# INA219Input.net
KiCad netlist of a schematic drawn in Altium Designer
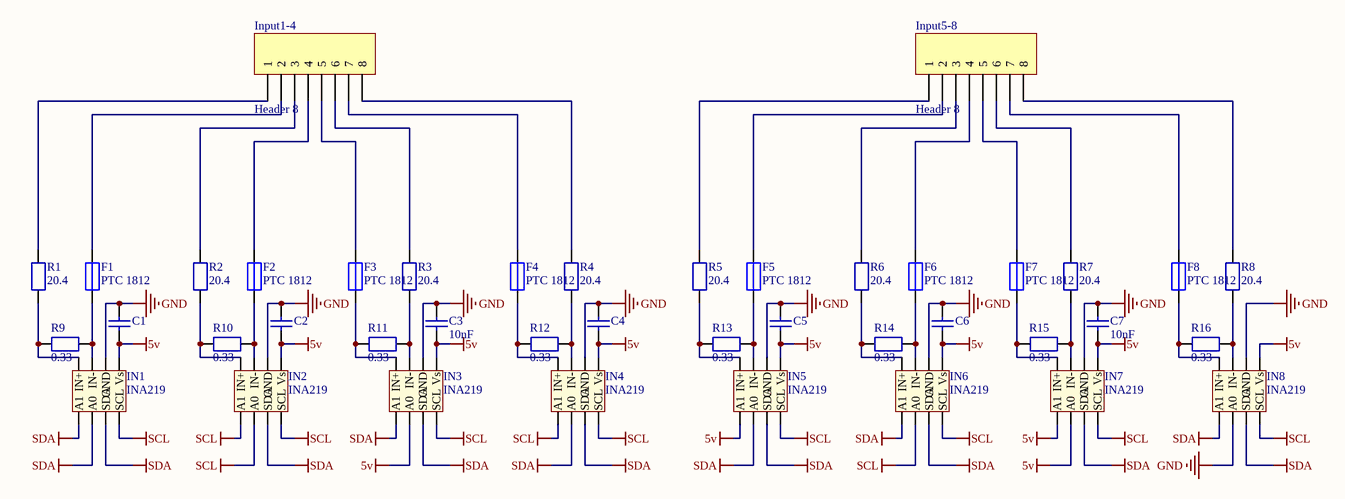
[diagram p0: INA219Input.SchDoc]

(export (version "E")
  (design (tool "Eeschema 10.0.6"))
  (components
    (comp (ref "C1")
      (value "~")
      (footprint "1\" ceramic Radial Cap")
      (description "1\" ceramic Radial Cap")
      (libsource (lib "Capacitors") (part "1{dblquote} ceramic Radial Cap"))
    )
    (comp (ref "C2")
      (value "~")
      (footprint "1\" ceramic Radial Cap")
      (description "1\" ceramic Radial Cap")
      (libsource (lib "Capacitors") (part "1{dblquote} ceramic Radial Cap"))
    )
    (comp (ref "C3")
      (value "10nF")
      (footprint "1\" ceramic Radial Cap")
      (description "1\" ceramic Radial Cap")
      (libsource (lib "Capacitors") (part "1{dblquote} ceramic Radial Cap"))
    )
    (comp (ref "C4")
      (value "~")
      (footprint "1\" ceramic Radial Cap")
      (description "1\" ceramic Radial Cap")
      (libsource (lib "Capacitors") (part "1{dblquote} ceramic Radial Cap"))
    )
    (comp (ref "C5")
      (value "~")
      (footprint "1\" ceramic Radial Cap")
      (description "1\" ceramic Radial Cap")
      (libsource (lib "Capacitors") (part "1{dblquote} ceramic Radial Cap"))
    )
    (comp (ref "C6")
      (value "~")
      (footprint "1\" ceramic Radial Cap")
      (description "1\" ceramic Radial Cap")
      (libsource (lib "Capacitors") (part "1{dblquote} ceramic Radial Cap"))
    )
    (comp (ref "C7")
      (value "10nF")
      (footprint "1\" ceramic Radial Cap")
      (description "1\" ceramic Radial Cap")
      (libsource (lib "Capacitors") (part "1{dblquote} ceramic Radial Cap"))
    )
    (comp (ref "F1")
      (value "PTC 1812")
      (footprint "0ZCG PTC 1812")
      (libsource (lib "Fuses") (part "PTC 1812 Bel Fuse"))
    )
    (comp (ref "F2")
      (value "PTC 1812")
      (footprint "0ZCG PTC 1812")
      (libsource (lib "Fuses") (part "PTC 1812 Bel Fuse"))
    )
    (comp (ref "F3")
      (value "PTC 1812")
      (footprint "0ZCG PTC 1812")
      (libsource (lib "Fuses") (part "PTC 1812 Bel Fuse"))
    )
    (comp (ref "F4")
      (value "PTC 1812")
      (footprint "0ZCG PTC 1812")
      (libsource (lib "Fuses") (part "PTC 1812 Bel Fuse"))
    )
    (comp (ref "F5")
      (value "PTC 1812")
      (footprint "0ZCG PTC 1812")
      (libsource (lib "Fuses") (part "PTC 1812 Bel Fuse"))
    )
    (comp (ref "F6")
      (value "PTC 1812")
      (footprint "0ZCG PTC 1812")
      (libsource (lib "Fuses") (part "PTC 1812 Bel Fuse"))
    )
    (comp (ref "F7")
      (value "PTC 1812")
      (footprint "0ZCG PTC 1812")
      (libsource (lib "Fuses") (part "PTC 1812 Bel Fuse"))
    )
    (comp (ref "F8")
      (value "PTC 1812")
      (footprint "0ZCG PTC 1812")
      (libsource (lib "Fuses") (part "PTC 1812 Bel Fuse"))
    )
    (comp (ref "IN1")
      (value "INA219")
      (footprint "INA219-D-SOIC")
      (libsource (lib "Miscellaneous IC's") (part "INA219-D-SOIC"))
    )
    (comp (ref "IN2")
      (value "INA219")
      (footprint "INA219-D-SOIC")
      (libsource (lib "Miscellaneous IC's") (part "INA219-D-SOIC"))
    )
    (comp (ref "IN3")
      (value "INA219")
      (footprint "INA219-D-SOIC")
      (libsource (lib "Miscellaneous IC's") (part "INA219-D-SOIC"))
    )
    (comp (ref "IN4")
      (value "INA219")
      (footprint "INA219-D-SOIC")
      (libsource (lib "Miscellaneous IC's") (part "INA219-D-SOIC"))
    )
    (comp (ref "IN5")
      (value "INA219")
      (footprint "INA219-D-SOIC")
      (libsource (lib "Miscellaneous IC's") (part "INA219-D-SOIC"))
    )
    (comp (ref "IN6")
      (value "INA219")
      (footprint "INA219-D-SOIC")
      (libsource (lib "Miscellaneous IC's") (part "INA219-D-SOIC"))
    )
    (comp (ref "IN7")
      (value "INA219")
      (footprint "INA219-D-SOIC")
      (libsource (lib "Miscellaneous IC's") (part "INA219-D-SOIC"))
    )
    (comp (ref "IN8")
      (value "INA219")
      (footprint "INA219-D-SOIC")
      (libsource (lib "Miscellaneous IC's") (part "INA219-D-SOIC"))
    )
    (comp (ref "Input1-4")
      (value "Header 8")
      (footprint "HDR1X8")
      (description "Header, 8-Pin")
      (fields (field (name "PUBLISHER") "Altium Limited"))
      (libsource (lib "Miscellaneous Connectors") (part "Header 8"))
    )
    (comp (ref "Input5-8")
      (value "Header 8")
      (footprint "HDR1X8")
      (description "Header, 8-Pin")
      (fields (field (name "PUBLISHER") "Altium Limited"))
      (libsource (lib "Miscellaneous Connectors") (part "Header 8"))
    )
    (comp (ref "R1")
      (value "20.4")
      (footprint "Axial 0.85 5W")
      (libsource (lib "Resistors") (part "Axial 0.85{dblquote} 5W"))
    )
    (comp (ref "R2")
      (value "20.4")
      (footprint "Axial 0.85 5W")
      (libsource (lib "Resistors") (part "Axial 0.85{dblquote} 5W"))
    )
    (comp (ref "R3")
      (value "20.4")
      (footprint "Axial 0.85 5W")
      (libsource (lib "Resistors") (part "Axial 0.85{dblquote} 5W"))
    )
    (comp (ref "R4")
      (value "20.4")
      (footprint "Axial 0.85 5W")
      (libsource (lib "Resistors") (part "Axial 0.85{dblquote} 5W"))
    )
    (comp (ref "R5")
      (value "20.4")
      (footprint "Axial 0.85 5W")
      (libsource (lib "Resistors") (part "Axial 0.85{dblquote} 5W"))
    )
    (comp (ref "R6")
      (value "20.4")
      (footprint "Axial 0.85 5W")
      (libsource (lib "Resistors") (part "Axial 0.85{dblquote} 5W"))
    )
    (comp (ref "R7")
      (value "20.4")
      (footprint "Axial 0.85 5W")
      (libsource (lib "Resistors") (part "Axial 0.85{dblquote} 5W"))
    )
    (comp (ref "R8")
      (value "20.4")
      (footprint "Axial 0.85 5W")
      (libsource (lib "Resistors") (part "Axial 0.85{dblquote} 5W"))
    )
    (comp (ref "R9")
      (value "0.33")
      (footprint "1206 SMD 1/4W")
      (libsource (lib "Resistors") (part "1206 SMD 1/4W"))
    )
    (comp (ref "R10")
      (value "0.33")
      (footprint "1206 SMD 1/4W")
      (libsource (lib "Resistors") (part "1206 SMD 1/4W"))
    )
    (comp (ref "R11")
      (value "0.33")
      (footprint "1206 SMD 1/4W")
      (libsource (lib "Resistors") (part "1206 SMD 1/4W"))
    )
    (comp (ref "R12")
      (value "0.33")
      (footprint "1206 SMD 1/4W")
      (libsource (lib "Resistors") (part "1206 SMD 1/4W"))
    )
    (comp (ref "R13")
      (value "0.33")
      (footprint "1206 SMD 1/4W")
      (libsource (lib "Resistors") (part "1206 SMD 1/4W"))
    )
    (comp (ref "R14")
      (value "0.33")
      (footprint "1206 SMD 1/4W")
      (libsource (lib "Resistors") (part "1206 SMD 1/4W"))
    )
    (comp (ref "R15")
      (value "0.33")
      (footprint "1206 SMD 1/4W")
      (libsource (lib "Resistors") (part "1206 SMD 1/4W"))
    )
    (comp (ref "R16")
      (value "0.33")
      (footprint "1206 SMD 1/4W")
      (libsource (lib "Resistors") (part "1206 SMD 1/4W"))
    )
  )
  (nets
    (net (code "1") (name "5v") (class "Default")
      (node (ref "C1") (pin "1") (pinfunction "1_1") (pintype "passive"))
      (node (ref "C2") (pin "1") (pinfunction "1_1") (pintype "passive"))
      (node (ref "C3") (pin "1") (pinfunction "1_1") (pintype "passive"))
      (node (ref "C4") (pin "1") (pinfunction "1_1") (pintype "passive"))
      (node (ref "C5") (pin "1") (pinfunction "1_1") (pintype "passive"))
      (node (ref "C6") (pin "1") (pinfunction "1_1") (pintype "passive"))
      (node (ref "C7") (pin "1") (pinfunction "1_1") (pintype "passive"))
      (node (ref "IN1") (pin "Vs") (pinfunction "Vs_Vs") (pintype "passive"))
      (node (ref "IN2") (pin "Vs") (pinfunction "Vs_Vs") (pintype "passive"))
      (node (ref "IN3") (pin "A0") (pinfunction "A0_A0") (pintype "passive"))
      (node (ref "IN3") (pin "Vs") (pinfunction "Vs_Vs") (pintype "passive"))
      (node (ref "IN4") (pin "Vs") (pinfunction "Vs_Vs") (pintype "passive"))
      (node (ref "IN5") (pin "A1") (pinfunction "A1_A1") (pintype "passive"))
      (node (ref "IN5") (pin "Vs") (pinfunction "Vs_Vs") (pintype "passive"))
      (node (ref "IN6") (pin "Vs") (pinfunction "Vs_Vs") (pintype "passive"))
      (node (ref "IN7") (pin "A0") (pinfunction "A0_A0") (pintype "passive"))
      (node (ref "IN7") (pin "A1") (pinfunction "A1_A1") (pintype "passive"))
      (node (ref "IN7") (pin "Vs") (pinfunction "Vs_Vs") (pintype "passive"))
      (node (ref "IN8") (pin "Vs") (pinfunction "Vs_Vs") (pintype "passive"))
    )
    (net (code "2") (name "GND") (class "Default")
      (node (ref "C1") (pin "2") (pinfunction "2_2") (pintype "passive"))
      (node (ref "C2") (pin "2") (pinfunction "2_2") (pintype "passive"))
      (node (ref "C3") (pin "2") (pinfunction "2_2") (pintype "passive"))
      (node (ref "C4") (pin "2") (pinfunction "2_2") (pintype "passive"))
      (node (ref "C5") (pin "2") (pinfunction "2_2") (pintype "passive"))
      (node (ref "C6") (pin "2") (pinfunction "2_2") (pintype "passive"))
      (node (ref "C7") (pin "2") (pinfunction "2_2") (pintype "passive"))
      (node (ref "IN1") (pin "GND") (pinfunction "GND_GND") (pintype "passive"))
      (node (ref "IN2") (pin "GND") (pinfunction "GND_GND") (pintype "passive"))
      (node (ref "IN3") (pin "GND") (pinfunction "GND_GND") (pintype "passive"))
      (node (ref "IN4") (pin "GND") (pinfunction "GND_GND") (pintype "passive"))
      (node (ref "IN5") (pin "GND") (pinfunction "GND_GND") (pintype "passive"))
      (node (ref "IN6") (pin "GND") (pinfunction "GND_GND") (pintype "passive"))
      (node (ref "IN7") (pin "GND") (pinfunction "GND_GND") (pintype "passive"))
      (node (ref "IN8") (pin "A0") (pinfunction "A0_A0") (pintype "passive"))
      (node (ref "IN8") (pin "GND") (pinfunction "GND_GND") (pintype "passive"))
    )
    (net (code "3") (name "Net-(F1-Pad1)") (class "Default")
      (node (ref "F1") (pin "1") (pinfunction "1_1") (pintype "passive"))
      (node (ref "IN1") (pin "IN-") (pinfunction "IN-_IN-") (pintype "passive"))
      (node (ref "R9") (pin "1") (pinfunction "1_1") (pintype "passive"))
    )
    (net (code "4") (name "Net-(F1-Pad2)") (class "Default")
      (node (ref "F1") (pin "2") (pinfunction "2_2") (pintype "passive"))
      (node (ref "Input1-4") (pin "2") (pinfunction "2_2") (pintype "passive"))
    )
    (net (code "5") (name "Net-(F2-Pad1)") (class "Default")
      (node (ref "F2") (pin "1") (pinfunction "1_1") (pintype "passive"))
      (node (ref "IN2") (pin "IN-") (pinfunction "IN-_IN-") (pintype "passive"))
      (node (ref "R10") (pin "1") (pinfunction "1_1") (pintype "passive"))
    )
    (net (code "6") (name "Net-(F2-Pad2)") (class "Default")
      (node (ref "F2") (pin "2") (pinfunction "2_2") (pintype "passive"))
      (node (ref "Input1-4") (pin "4") (pinfunction "4_4") (pintype "passive"))
    )
    (net (code "7") (name "Net-(F3-Pad1)") (class "Default")
      (node (ref "F3") (pin "1") (pinfunction "1_1") (pintype "passive"))
      (node (ref "IN3") (pin "IN+") (pinfunction "IN+_IN+") (pintype "passive"))
      (node (ref "R11") (pin "2") (pinfunction "2_2") (pintype "passive"))
    )
    (net (code "8") (name "Net-(F3-Pad2)") (class "Default")
      (node (ref "F3") (pin "2") (pinfunction "2_2") (pintype "passive"))
      (node (ref "Input1-4") (pin "5") (pinfunction "5_5") (pintype "passive"))
    )
    (net (code "9") (name "Net-(F4-Pad1)") (class "Default")
      (node (ref "F4") (pin "1") (pinfunction "1_1") (pintype "passive"))
      (node (ref "IN4") (pin "IN+") (pinfunction "IN+_IN+") (pintype "passive"))
      (node (ref "R12") (pin "2") (pinfunction "2_2") (pintype "passive"))
    )
    (net (code "10") (name "Net-(F4-Pad2)") (class "Default")
      (node (ref "F4") (pin "2") (pinfunction "2_2") (pintype "passive"))
      (node (ref "Input1-4") (pin "7") (pinfunction "7_7") (pintype "passive"))
    )
    (net (code "11") (name "Net-(F5-Pad1)") (class "Default")
      (node (ref "F5") (pin "1") (pinfunction "1_1") (pintype "passive"))
      (node (ref "IN5") (pin "IN-") (pinfunction "IN-_IN-") (pintype "passive"))
      (node (ref "R13") (pin "1") (pinfunction "1_1") (pintype "passive"))
    )
    (net (code "12") (name "Net-(F5-Pad2)") (class "Default")
      (node (ref "F5") (pin "2") (pinfunction "2_2") (pintype "passive"))
      (node (ref "Input5-8") (pin "2") (pinfunction "2_2") (pintype "passive"))
    )
    (net (code "13") (name "Net-(F6-Pad1)") (class "Default")
      (node (ref "F6") (pin "1") (pinfunction "1_1") (pintype "passive"))
      (node (ref "IN6") (pin "IN-") (pinfunction "IN-_IN-") (pintype "passive"))
      (node (ref "R14") (pin "1") (pinfunction "1_1") (pintype "passive"))
    )
    (net (code "14") (name "Net-(F6-Pad2)") (class "Default")
      (node (ref "F6") (pin "2") (pinfunction "2_2") (pintype "passive"))
      (node (ref "Input5-8") (pin "4") (pinfunction "4_4") (pintype "passive"))
    )
    (net (code "15") (name "Net-(F7-Pad1)") (class "Default")
      (node (ref "F7") (pin "1") (pinfunction "1_1") (pintype "passive"))
      (node (ref "IN7") (pin "IN+") (pinfunction "IN+_IN+") (pintype "passive"))
      (node (ref "R15") (pin "2") (pinfunction "2_2") (pintype "passive"))
    )
    (net (code "16") (name "Net-(F7-Pad2)") (class "Default")
      (node (ref "F7") (pin "2") (pinfunction "2_2") (pintype "passive"))
      (node (ref "Input5-8") (pin "5") (pinfunction "5_5") (pintype "passive"))
    )
    (net (code "17") (name "Net-(F8-Pad1)") (class "Default")
      (node (ref "F8") (pin "1") (pinfunction "1_1") (pintype "passive"))
      (node (ref "IN8") (pin "IN+") (pinfunction "IN+_IN+") (pintype "passive"))
      (node (ref "R16") (pin "2") (pinfunction "2_2") (pintype "passive"))
    )
    (net (code "18") (name "Net-(F8-Pad2)") (class "Default")
      (node (ref "F8") (pin "2") (pinfunction "2_2") (pintype "passive"))
      (node (ref "Input5-8") (pin "7") (pinfunction "7_7") (pintype "passive"))
    )
    (net (code "19") (name "Net-(IN1-PadIN+)") (class "Default")
      (node (ref "IN1") (pin "IN+") (pinfunction "IN+_IN+") (pintype "passive"))
      (node (ref "R1") (pin "1") (pinfunction "1_1") (pintype "passive"))
      (node (ref "R9") (pin "2") (pinfunction "2_2") (pintype "passive"))
    )
    (net (code "20") (name "Net-(IN2-PadIN+)") (class "Default")
      (node (ref "IN2") (pin "IN+") (pinfunction "IN+_IN+") (pintype "passive"))
      (node (ref "R10") (pin "2") (pinfunction "2_2") (pintype "passive"))
      (node (ref "R2") (pin "1") (pinfunction "1_1") (pintype "passive"))
    )
    (net (code "21") (name "Net-(IN3-PadIN-)") (class "Default")
      (node (ref "IN3") (pin "IN-") (pinfunction "IN-_IN-") (pintype "passive"))
      (node (ref "R11") (pin "1") (pinfunction "1_1") (pintype "passive"))
      (node (ref "R3") (pin "1") (pinfunction "1_1") (pintype "passive"))
    )
    (net (code "22") (name "Net-(IN4-PadIN-)") (class "Default")
      (node (ref "IN4") (pin "IN-") (pinfunction "IN-_IN-") (pintype "passive"))
      (node (ref "R12") (pin "1") (pinfunction "1_1") (pintype "passive"))
      (node (ref "R4") (pin "1") (pinfunction "1_1") (pintype "passive"))
    )
    (net (code "23") (name "Net-(IN5-PadIN+)") (class "Default")
      (node (ref "IN5") (pin "IN+") (pinfunction "IN+_IN+") (pintype "passive"))
      (node (ref "R13") (pin "2") (pinfunction "2_2") (pintype "passive"))
      (node (ref "R5") (pin "1") (pinfunction "1_1") (pintype "passive"))
    )
    (net (code "24") (name "Net-(IN6-PadIN+)") (class "Default")
      (node (ref "IN6") (pin "IN+") (pinfunction "IN+_IN+") (pintype "passive"))
      (node (ref "R14") (pin "2") (pinfunction "2_2") (pintype "passive"))
      (node (ref "R6") (pin "1") (pinfunction "1_1") (pintype "passive"))
    )
    (net (code "25") (name "Net-(IN7-PadIN-)") (class "Default")
      (node (ref "IN7") (pin "IN-") (pinfunction "IN-_IN-") (pintype "passive"))
      (node (ref "R15") (pin "1") (pinfunction "1_1") (pintype "passive"))
      (node (ref "R7") (pin "1") (pinfunction "1_1") (pintype "passive"))
    )
    (net (code "26") (name "Net-(IN8-PadIN-)") (class "Default")
      (node (ref "IN8") (pin "IN-") (pinfunction "IN-_IN-") (pintype "passive"))
      (node (ref "R16") (pin "1") (pinfunction "1_1") (pintype "passive"))
      (node (ref "R8") (pin "1") (pinfunction "1_1") (pintype "passive"))
    )
    (net (code "27") (name "Net-(Input1-4-Pad1)") (class "Default")
      (node (ref "Input1-4") (pin "1") (pinfunction "1_1") (pintype "passive"))
      (node (ref "R1") (pin "2") (pinfunction "2_2") (pintype "passive"))
    )
    (net (code "28") (name "Net-(Input1-4-Pad3)") (class "Default")
      (node (ref "Input1-4") (pin "3") (pinfunction "3_3") (pintype "passive"))
      (node (ref "R2") (pin "2") (pinfunction "2_2") (pintype "passive"))
    )
    (net (code "29") (name "Net-(Input1-4-Pad6)") (class "Default")
      (node (ref "Input1-4") (pin "6") (pinfunction "6_6") (pintype "passive"))
      (node (ref "R3") (pin "2") (pinfunction "2_2") (pintype "passive"))
    )
    (net (code "30") (name "Net-(Input1-4-Pad8)") (class "Default")
      (node (ref "Input1-4") (pin "8") (pinfunction "8_8") (pintype "passive"))
      (node (ref "R4") (pin "2") (pinfunction "2_2") (pintype "passive"))
    )
    (net (code "31") (name "Net-(Input5-8-Pad1)") (class "Default")
      (node (ref "Input5-8") (pin "1") (pinfunction "1_1") (pintype "passive"))
      (node (ref "R5") (pin "2") (pinfunction "2_2") (pintype "passive"))
    )
    (net (code "32") (name "Net-(Input5-8-Pad3)") (class "Default")
      (node (ref "Input5-8") (pin "3") (pinfunction "3_3") (pintype "passive"))
      (node (ref "R6") (pin "2") (pinfunction "2_2") (pintype "passive"))
    )
    (net (code "33") (name "Net-(Input5-8-Pad6)") (class "Default")
      (node (ref "Input5-8") (pin "6") (pinfunction "6_6") (pintype "passive"))
      (node (ref "R7") (pin "2") (pinfunction "2_2") (pintype "passive"))
    )
    (net (code "34") (name "Net-(Input5-8-Pad8)") (class "Default")
      (node (ref "Input5-8") (pin "8") (pinfunction "8_8") (pintype "passive"))
      (node (ref "R8") (pin "2") (pinfunction "2_2") (pintype "passive"))
    )
    (net (code "35") (name "SCL") (class "Default")
      (node (ref "IN1") (pin "SCL") (pinfunction "SCL_SCL") (pintype "passive"))
      (node (ref "IN2") (pin "A0") (pinfunction "A0_A0") (pintype "passive"))
      (node (ref "IN2") (pin "A1") (pinfunction "A1_A1") (pintype "passive"))
      (node (ref "IN2") (pin "SCL") (pinfunction "SCL_SCL") (pintype "passive"))
      (node (ref "IN3") (pin "SCL") (pinfunction "SCL_SCL") (pintype "passive"))
      (node (ref "IN4") (pin "A1") (pinfunction "A1_A1") (pintype "passive"))
      (node (ref "IN4") (pin "SCL") (pinfunction "SCL_SCL") (pintype "passive"))
      (node (ref "IN5") (pin "SCL") (pinfunction "SCL_SCL") (pintype "passive"))
      (node (ref "IN6") (pin "A0") (pinfunction "A0_A0") (pintype "passive"))
      (node (ref "IN6") (pin "SCL") (pinfunction "SCL_SCL") (pintype "passive"))
      (node (ref "IN7") (pin "SCL") (pinfunction "SCL_SCL") (pintype "passive"))
      (node (ref "IN8") (pin "SCL") (pinfunction "SCL_SCL") (pintype "passive"))
    )
    (net (code "36") (name "SDA") (class "Default")
      (node (ref "IN1") (pin "A0") (pinfunction "A0_A0") (pintype "passive"))
      (node (ref "IN1") (pin "A1") (pinfunction "A1_A1") (pintype "passive"))
      (node (ref "IN1") (pin "SDA") (pinfunction "SDA_SDA") (pintype "passive"))
      (node (ref "IN2") (pin "SDA") (pinfunction "SDA_SDA") (pintype "passive"))
      (node (ref "IN3") (pin "A1") (pinfunction "A1_A1") (pintype "passive"))
      (node (ref "IN3") (pin "SDA") (pinfunction "SDA_SDA") (pintype "passive"))
      (node (ref "IN4") (pin "A0") (pinfunction "A0_A0") (pintype "passive"))
      (node (ref "IN4") (pin "SDA") (pinfunction "SDA_SDA") (pintype "passive"))
      (node (ref "IN5") (pin "A0") (pinfunction "A0_A0") (pintype "passive"))
      (node (ref "IN5") (pin "SDA") (pinfunction "SDA_SDA") (pintype "passive"))
      (node (ref "IN6") (pin "A1") (pinfunction "A1_A1") (pintype "passive"))
      (node (ref "IN6") (pin "SDA") (pinfunction "SDA_SDA") (pintype "passive"))
      (node (ref "IN7") (pin "SDA") (pinfunction "SDA_SDA") (pintype "passive"))
      (node (ref "IN8") (pin "A1") (pinfunction "A1_A1") (pintype "passive"))
      (node (ref "IN8") (pin "SDA") (pinfunction "SDA_SDA") (pintype "passive"))
    )
  )
)
